# vialShine.net
KiCad netlist of a schematic drawn in EAGLE
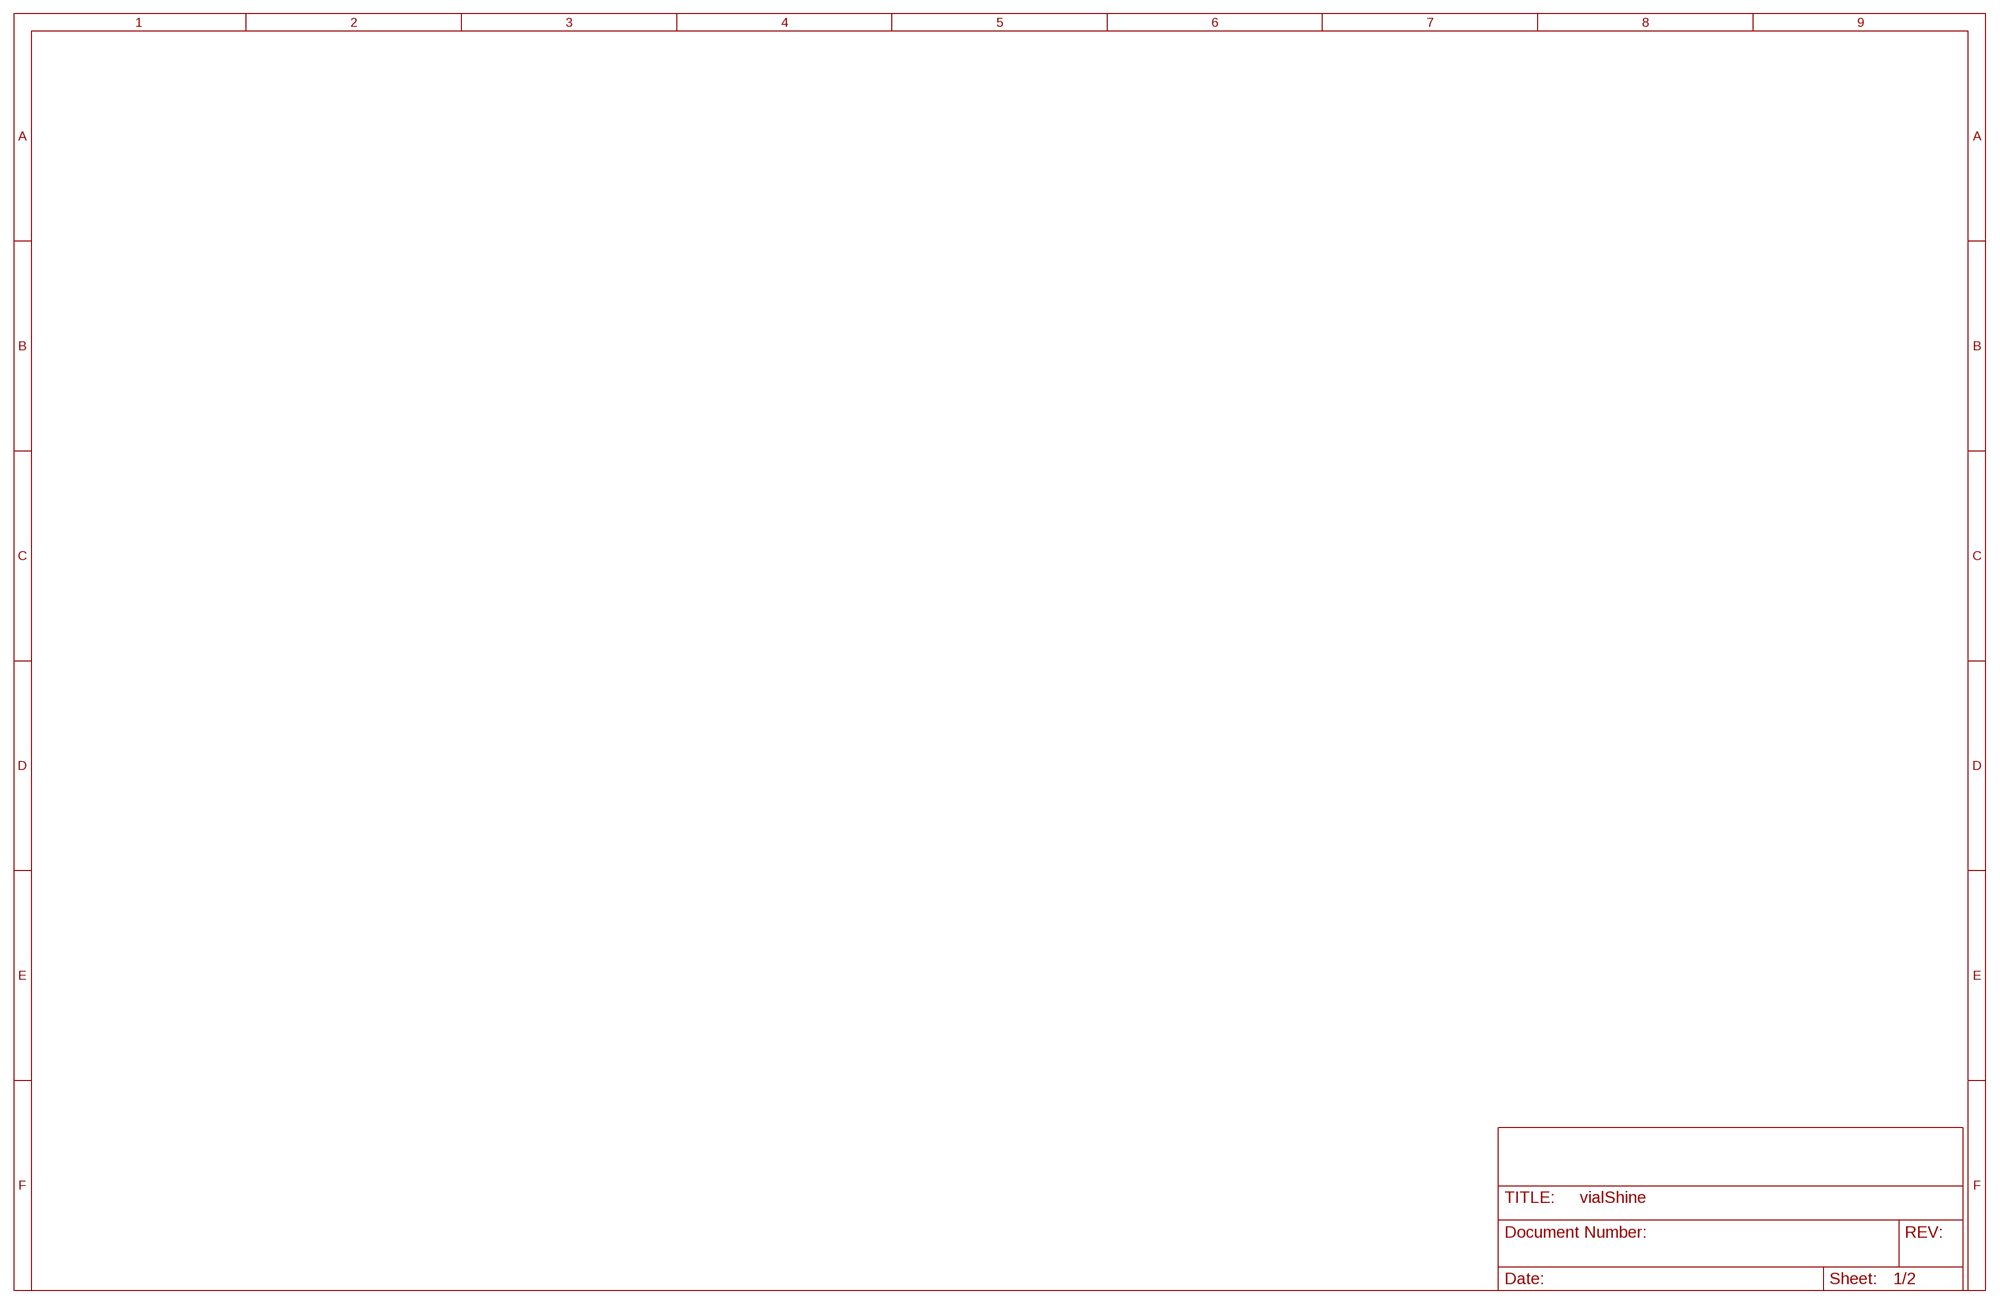
[diagram p0: schematic, sheet 1]
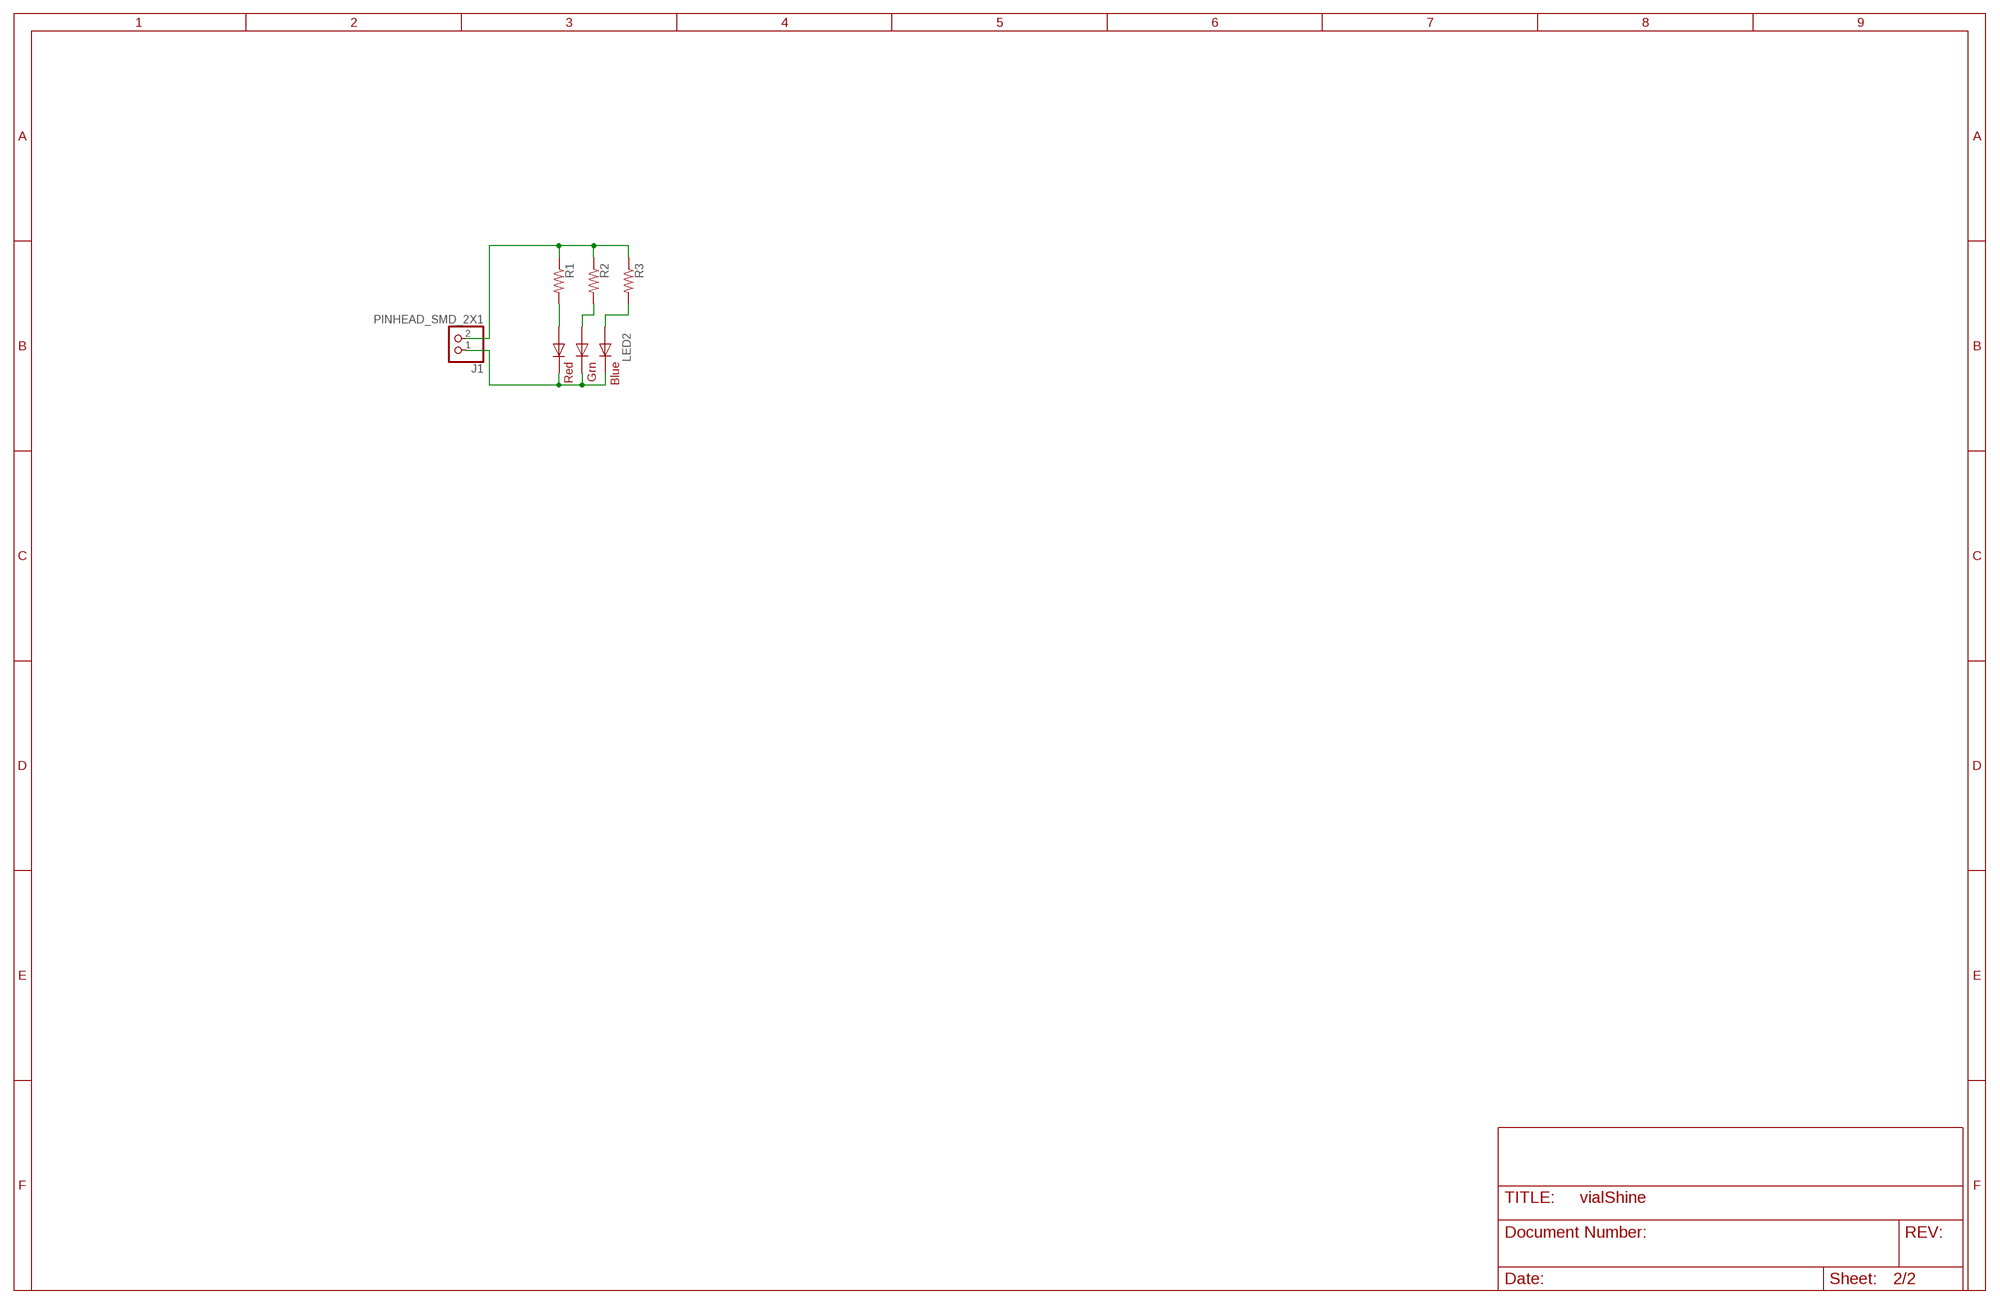
[diagram p1: schematic, sheet 2]

(export (version "E")
  (design (tool "Eeschema 10.0.6"))
  (components
    (comp (ref "J1")
      (value "PINHEAD_SMD_2X1")
      (footprint "eagle-import:PINHEAD_SMD_2X1")
      (libsource (lib "eagle-import") (part "PINHEAD_SMD_2X1"))
    )
    (comp (ref "LED2")
      (value "RGBLED5050")
      (footprint "eagle-import:RGBLED5050")
      (libsource (lib "eagle-import") (part "RGBLED5050"))
    )
    (comp (ref "R1")
      (value "R-US_R0603")
      (footprint "eagle-import:R0603")
      (libsource (lib "eagle-import") (part "R-US_R0603"))
    )
    (comp (ref "R2")
      (value "R-US_R0603")
      (footprint "eagle-import:R0603")
      (libsource (lib "eagle-import") (part "R-US_R0603"))
    )
    (comp (ref "R3")
      (value "R-US_R0603")
      (footprint "eagle-import:R0603")
      (libsource (lib "eagle-import") (part "R-US_R0603"))
    )
  )
  (nets
    (net (code "1") (name "Net-(J1-Pad2)") (class "Default")
      (node (ref "J1") (pin "2") (pinfunction "2_2") (pintype "passive"))
      (node (ref "R1") (pin "1") (pinfunction "1_1") (pintype "passive"))
      (node (ref "R2") (pin "1") (pinfunction "1_1") (pintype "passive"))
      (node (ref "R3") (pin "1") (pinfunction "1_1") (pintype "passive"))
    )
    (net (code "2") (name "Net-(LED2-BLUE_A)") (class "Default")
      (node (ref "LED2") (pin "3") (pinfunction "BLUE_A_3") (pintype "bidirectional"))
      (node (ref "R3") (pin "2") (pinfunction "2_2") (pintype "passive"))
    )
    (net (code "3") (name "Net-(LED2-BLUE_C)") (class "Default")
      (node (ref "J1") (pin "1") (pinfunction "1_1") (pintype "passive"))
      (node (ref "LED2") (pin "4") (pinfunction "BLUE_C_4") (pintype "bidirectional"))
      (node (ref "LED2") (pin "5") (pinfunction "RED_C_5") (pintype "bidirectional"))
      (node (ref "LED2") (pin "6") (pinfunction "GREEN_C_6") (pintype "bidirectional"))
    )
    (net (code "4") (name "Net-(LED2-GREEN_A)") (class "Default")
      (node (ref "LED2") (pin "1") (pinfunction "GREEN_A_1") (pintype "bidirectional"))
      (node (ref "R2") (pin "2") (pinfunction "2_2") (pintype "passive"))
    )
    (net (code "5") (name "Net-(LED2-RED_A)") (class "Default")
      (node (ref "LED2") (pin "2") (pinfunction "RED_A_2") (pintype "bidirectional"))
      (node (ref "R1") (pin "2") (pinfunction "2_2") (pintype "passive"))
    )
  )
)
